# Sheet1.net
KiCad netlist of a schematic drawn in Altium Designer
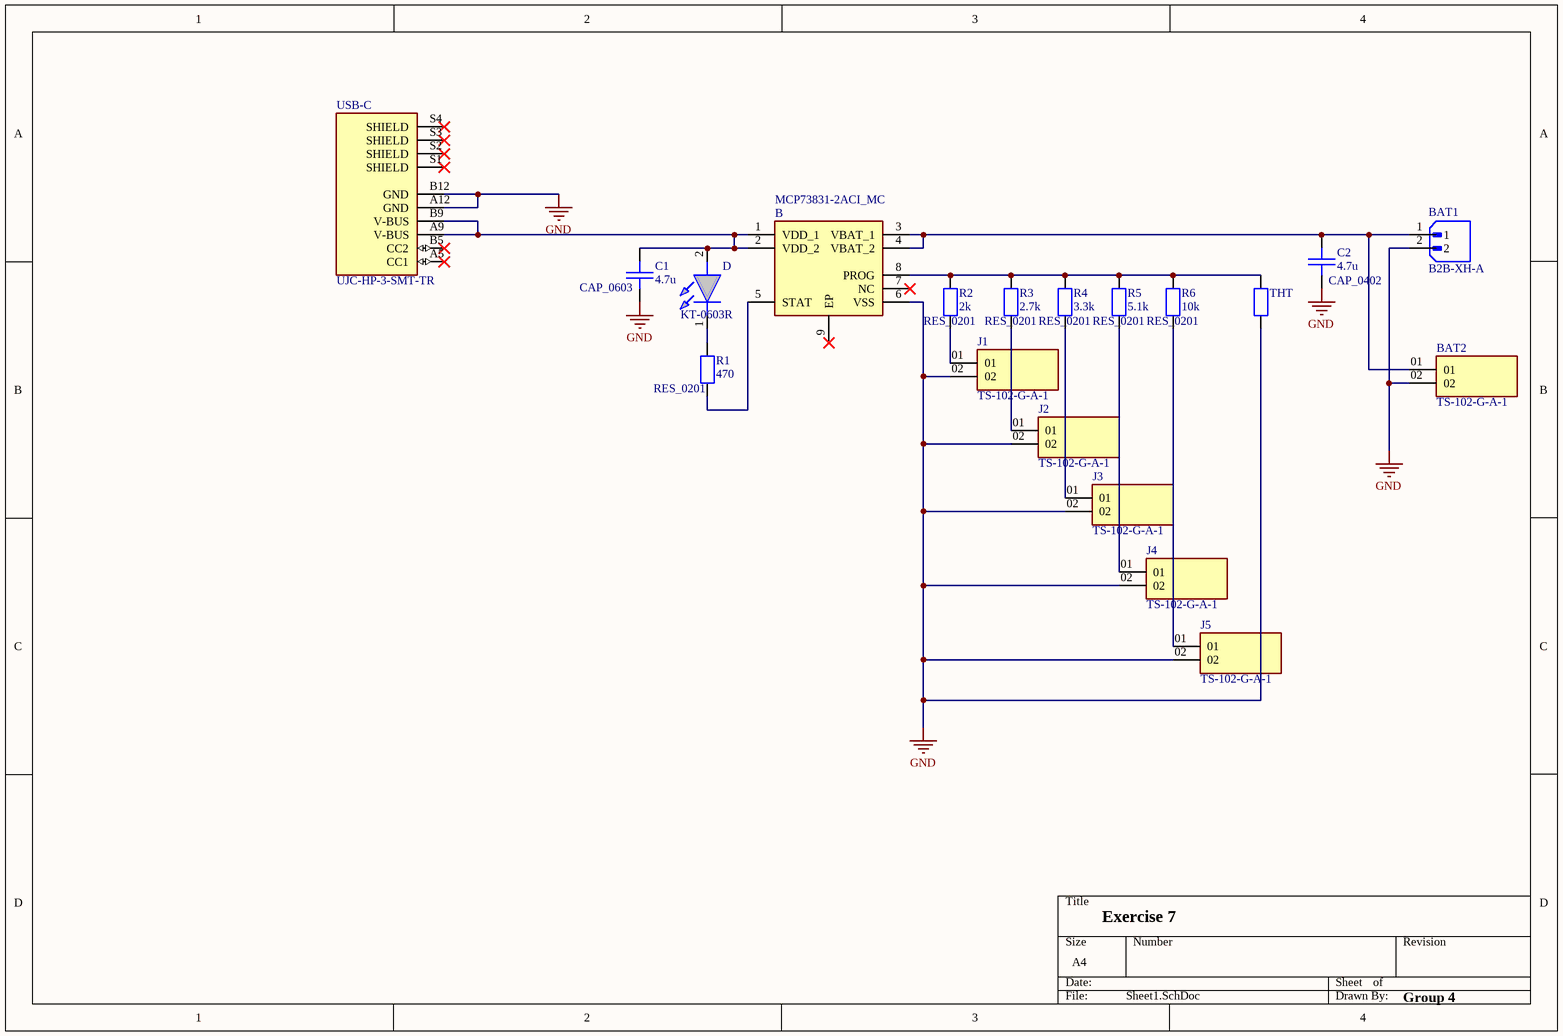
[diagram p0: Sheet1.SchDoc]

(export (version "E")
  (design (tool "Eeschema 10.0.6"))
  (components
    (comp (ref "B")
      (value "MCP73831-2ACI_MC")
      (footprint "SON50P300X200X100-9N-D")
      (description "Microchip MCP73831-2ACI/MC, Battery Charge Controller Lithium-Ion, Lithium-Polymer, 8-pin DFN")
      (fields
        (field (name "MANUFACTURER_PART_NUMBER") "MCP73831-2ACI/MC")
        (field (name "MOUSER PART NUMBER") "579-MCP73831-2ACI/MC")
      )
      (libsource (lib "MCP73831-2ACI_MC") (part "MCP73831-2ACI_MC"))
    )
    (comp (ref "BAT1")
      (value "B2B-XH-A")
      (footprint "JST_B2B-XH-A")
      (fields (field (name "MF") "{'manufacturer': u'JST Sales America Inc.'}"))
      (libsource (lib "B2B-XH-A") (part "B2B-XH-A"))
    )
    (comp (ref "BAT2")
      (value "TS-102-G-A-1")
      (footprint "SAMTEC_TS-102-G-A-1")
      (fields (field (name "MF") "{'manufacturer': u'Samtec Inc.'}"))
      (libsource (lib "TS-102-G-A-1") (part "TS-102-G-A-1"))
    )
    (comp (ref "C1")
      (value "CAP_0603")
      (footprint "CAP_0603")
      (fields (field (name "ALTIUM_VALUE") "4.7u"))
      (libsource (lib "smd_sch_lib") (part "CAP_0603"))
    )
    (comp (ref "C2")
      (value "CAP_0402")
      (footprint "CAP_0402")
      (fields (field (name "ALTIUM_VALUE") "4.7u"))
      (libsource (lib "smd_sch_lib") (part "CAP_0402"))
    )
    (comp (ref "D")
      (value "KT-0603R")
      (footprint "LEDC1608X70N")
      (description "Red 615~630nm 1.9~2.2V 0603 Light Emitting Diodes (LED) RoHS")
      (libsource (lib "LED_KT-0603R") (part "KT-0603R"))
    )
    (comp (ref "J1")
      (value "TS-102-G-A-1")
      (footprint "SAMTEC_TS-102-G-A-1")
      (fields (field (name "MF") "{'manufacturer': u'Samtec Inc.'}"))
      (libsource (lib "Victor Hald") (part "TS-102-G-A-1"))
    )
    (comp (ref "J2")
      (value "TS-102-G-A-1")
      (footprint "SAMTEC_TS-102-G-A-1")
      (fields (field (name "MF") "{'manufacturer': u'Samtec Inc.'}"))
      (libsource (lib "Victor Hald") (part "TS-102-G-A-1"))
    )
    (comp (ref "J3")
      (value "TS-102-G-A-1")
      (footprint "SAMTEC_TS-102-G-A-1")
      (fields (field (name "MF") "{'manufacturer': u'Samtec Inc.'}"))
      (libsource (lib "Victor Hald") (part "TS-102-G-A-1"))
    )
    (comp (ref "J4")
      (value "TS-102-G-A-1")
      (footprint "SAMTEC_TS-102-G-A-1")
      (fields (field (name "MF") "{'manufacturer': u'Samtec Inc.'}"))
      (libsource (lib "Victor Hald") (part "TS-102-G-A-1"))
    )
    (comp (ref "J5")
      (value "TS-102-G-A-1")
      (footprint "SAMTEC_TS-102-G-A-1")
      (fields (field (name "MF") "{'manufacturer': u'Samtec Inc.'}"))
      (libsource (lib "Victor Hald") (part "TS-102-G-A-1"))
    )
    (comp (ref "R1")
      (value "RES_0201")
      (footprint "RES_0201")
      (fields (field (name "ALTIUM_VALUE") "470"))
      (libsource (lib "smd_sch_lib") (part "RES_0201"))
    )
    (comp (ref "R2")
      (value "RES_0201")
      (footprint "RES_0201")
      (fields (field (name "ALTIUM_VALUE") "2k"))
      (libsource (lib "smd_sch_lib") (part "RES_0201"))
    )
    (comp (ref "R3")
      (value "RES_0201")
      (footprint "RES_0201")
      (fields (field (name "ALTIUM_VALUE") "2.7k"))
      (libsource (lib "smd_sch_lib") (part "RES_0201"))
    )
    (comp (ref "R4")
      (value "RES_0201")
      (footprint "RES_0201")
      (fields (field (name "ALTIUM_VALUE") "3.3k"))
      (libsource (lib "smd_sch_lib") (part "RES_0201"))
    )
    (comp (ref "R5")
      (value "RES_0201")
      (footprint "RES_0201")
      (fields (field (name "ALTIUM_VALUE") "5.1k"))
      (libsource (lib "smd_sch_lib") (part "RES_0201"))
    )
    (comp (ref "R6")
      (value "RES_0201")
      (footprint "RES_0201")
      (fields (field (name "ALTIUM_VALUE") "10k"))
      (libsource (lib "smd_sch_lib") (part "RES_0201"))
    )
    (comp (ref "THT")
      (value "~")
      (footprint "PCBComponent_1")
      (libsource (lib "res_tht_sym_lib") (part "R_THT"))
    )
    (comp (ref "USB-C")
      (value "UJC-HP-3-SMT-TR")
      (footprint "CUI_UJC-HP-3-SMT-TR")
      (libsource (lib "UJC-HP-3-SMT-TR") (part "UJC-HP-3-SMT-TR"))
    )
  )
  (nets
    (net (code "1") (name "GND") (class "Default")
      (node (ref "B") (pin "6") (pinfunction "VSS_6") (pintype "passive"))
      (node (ref "BAT1") (pin "2") (pinfunction "2_2") (pintype "passive"))
      (node (ref "BAT2") (pin "02") (pinfunction "02_02") (pintype "passive"))
      (node (ref "C1") (pin "1") (pintype "passive"))
      (node (ref "C2") (pin "1") (pintype "passive"))
      (node (ref "J1") (pin "02") (pinfunction "02_02") (pintype "passive"))
      (node (ref "J2") (pin "02") (pinfunction "02_02") (pintype "passive"))
      (node (ref "J3") (pin "02") (pinfunction "02_02") (pintype "passive"))
      (node (ref "J4") (pin "02") (pinfunction "02_02") (pintype "passive"))
      (node (ref "J5") (pin "02") (pinfunction "02_02") (pintype "passive"))
      (node (ref "THT") (pin "1") (pinfunction "1_1") (pintype "passive"))
      (node (ref "USB-C") (pin "A12") (pinfunction "GND_A12") (pintype "power_in"))
      (node (ref "USB-C") (pin "B12") (pinfunction "GND_B12") (pintype "power_in"))
    )
    (net (code "2") (name "Net-(B-PROG)") (class "Default")
      (node (ref "B") (pin "8") (pinfunction "PROG_8") (pintype "passive"))
      (node (ref "R2") (pin "2") (pintype "passive"))
      (node (ref "R3") (pin "2") (pintype "passive"))
      (node (ref "R4") (pin "2") (pintype "passive"))
      (node (ref "R5") (pin "2") (pintype "passive"))
      (node (ref "R6") (pin "2") (pintype "passive"))
      (node (ref "THT") (pin "2") (pinfunction "2_2") (pintype "passive"))
    )
    (net (code "3") (name "Net-(B-STAT)") (class "Default")
      (node (ref "B") (pin "5") (pinfunction "STAT_5") (pintype "passive"))
      (node (ref "R1") (pin "1") (pintype "passive"))
    )
    (net (code "4") (name "Net-(B-VBAT_1)") (class "Default")
      (node (ref "B") (pin "3") (pinfunction "VBAT_1_3") (pintype "passive"))
      (node (ref "B") (pin "4") (pinfunction "VBAT_2_4") (pintype "passive"))
      (node (ref "BAT1") (pin "1") (pinfunction "1_1") (pintype "passive"))
      (node (ref "BAT2") (pin "01") (pinfunction "01_01") (pintype "passive"))
      (node (ref "C2") (pin "2") (pintype "passive"))
    )
    (net (code "5") (name "Net-(B-VDD_1)") (class "Default")
      (node (ref "B") (pin "1") (pinfunction "VDD_1_1") (pintype "passive"))
      (node (ref "B") (pin "2") (pinfunction "VDD_2_2") (pintype "passive"))
      (node (ref "C1") (pin "2") (pintype "passive"))
      (node (ref "D") (pin "2") (pinfunction "A_2") (pintype "passive"))
      (node (ref "USB-C") (pin "A9") (pinfunction "V-BUS_A9") (pintype "power_in"))
      (node (ref "USB-C") (pin "B9") (pinfunction "V-BUS_B9") (pintype "power_in"))
    )
    (net (code "6") (name "Net-(D-K)") (class "Default")
      (node (ref "D") (pin "1") (pinfunction "K_1") (pintype "passive"))
      (node (ref "R1") (pin "2") (pintype "passive"))
    )
    (net (code "7") (name "Net-(J1-Pad01)") (class "Default")
      (node (ref "J1") (pin "01") (pinfunction "01_01") (pintype "passive"))
      (node (ref "R2") (pin "1") (pintype "passive"))
    )
    (net (code "8") (name "Net-(J2-Pad01)") (class "Default")
      (node (ref "J2") (pin "01") (pinfunction "01_01") (pintype "passive"))
      (node (ref "R3") (pin "1") (pintype "passive"))
    )
    (net (code "9") (name "Net-(J3-Pad01)") (class "Default")
      (node (ref "J3") (pin "01") (pinfunction "01_01") (pintype "passive"))
      (node (ref "R4") (pin "1") (pintype "passive"))
    )
    (net (code "10") (name "Net-(J4-Pad01)") (class "Default")
      (node (ref "J4") (pin "01") (pinfunction "01_01") (pintype "passive"))
      (node (ref "R5") (pin "1") (pintype "passive"))
    )
    (net (code "11") (name "Net-(J5-Pad01)") (class "Default")
      (node (ref "J5") (pin "01") (pinfunction "01_01") (pintype "passive"))
      (node (ref "R6") (pin "1") (pintype "passive"))
    )
    (net (code "12") (name "unconnected-(B-EP-Pad9)") (class "Default")
      (node (ref "B") (pin "9") (pinfunction "EP_9") (pintype "passive+no_connect"))
    )
    (net (code "13") (name "unconnected-(B-NC-Pad7)") (class "Default")
      (node (ref "B") (pin "7") (pinfunction "NC_7") (pintype "passive+no_connect"))
    )
    (net (code "14") (name "unconnected-(USB-C-CC1-PadA5)") (class "Default")
      (node (ref "USB-C") (pin "A5") (pinfunction "CC1_A5") (pintype "bidirectional+no_connect"))
    )
    (net (code "15") (name "unconnected-(USB-C-CC2-PadB5)") (class "Default")
      (node (ref "USB-C") (pin "B5") (pinfunction "CC2_B5") (pintype "bidirectional+no_connect"))
    )
    (net (code "16") (name "unconnected-(USB-C-SHIELD-PadS1)") (class "Default")
      (node (ref "USB-C") (pin "S1") (pinfunction "SHIELD_S1") (pintype "passive+no_connect"))
    )
    (net (code "17") (name "unconnected-(USB-C-SHIELD-PadS2)") (class "Default")
      (node (ref "USB-C") (pin "S2") (pinfunction "SHIELD_S2") (pintype "passive+no_connect"))
    )
    (net (code "18") (name "unconnected-(USB-C-SHIELD-PadS3)") (class "Default")
      (node (ref "USB-C") (pin "S3") (pinfunction "SHIELD_S3") (pintype "passive+no_connect"))
    )
    (net (code "19") (name "unconnected-(USB-C-SHIELD-PadS4)") (class "Default")
      (node (ref "USB-C") (pin "S4") (pinfunction "SHIELD_S4") (pintype "passive+no_connect"))
    )
  )
)
